# SensorBoard.net
KiCad netlist of a schematic drawn in Altium Designer
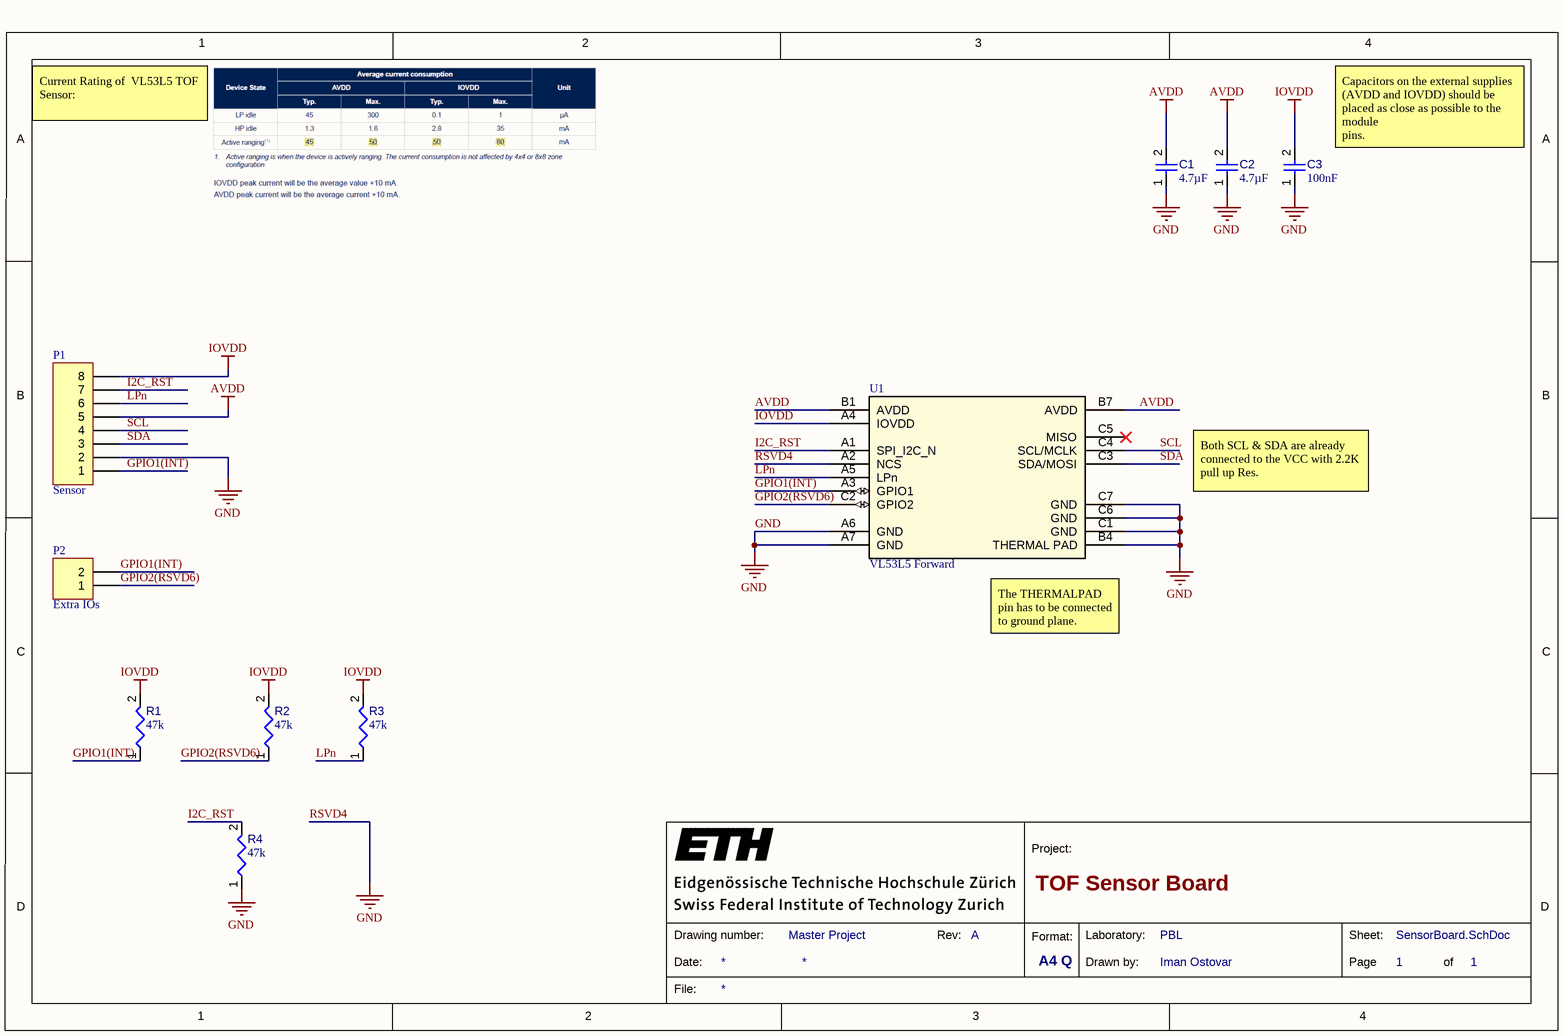
[diagram p0: SensorBoard.SchDoc]

(export (version "E")
  (design (tool "Eeschema 10.0.6"))
  (components
    (comp (ref "C1")
      (value "4.7µF")
      (footprint "CAPC1005X55X25ML5T10")
      (description "Chip Capacitor, 1 uF, +/- 10%, 6.3 V, 1005 (0402 Metric)")
      (fields (field (name "TOLERANCE") "10%") (field (name "Comment") "Capacitor 1 uF +/- 10% 6.3 V 1005"))
      (libsource (lib "ETH Zurich") (part "CAP-NP-2"))
    )
    (comp (ref "C2")
      (value "4.7µF")
      (footprint "CAPC1005X55X25ML5T10")
      (description "Chip Capacitor, 1 uF, +/- 10%, 6.3 V, 1005 (0402 Metric)")
      (fields (field (name "TOLERANCE") "10%") (field (name "Comment") "Capacitor 1 uF +/- 10% 6.3 V 1005"))
      (libsource (lib "ETH Zurich") (part "CAP-NP-2"))
    )
    (comp (ref "C3")
      (value "100nF")
      (footprint "CAPC0402(1005)60_L")
      (description "Chip Capacitor, 100nF +/-20%, 25V, 0402, Thickness 0.6 mm")
      (fields (field (name "TOLERANCE") "10%") (field (name "Comment") "Capacitor 100nF +/-20% 25V 0402"))
      (libsource (lib "ETH Zurich") (part "CAP-NP-2"))
    )
    (comp (ref "P1")
      (value "Sensor")
      (footprint "MHDR1X8")
      (description "Header, 8-Pin")
      (fields (field (name "PUBLISHER") "Altium Limited"))
      (libsource (lib "Miscellaneous Connectors") (part "MHDR1X8"))
    )
    (comp (ref "P2")
      (value "Extra IOs")
      (footprint "MHDR1X2")
      (description "Header, 2-Pin")
      (fields (field (name "PUBLISHER") "Altium Limited"))
      (libsource (lib "Miscellaneous Connectors") (part "MHDR1X2"))
    )
    (comp (ref "R1")
      (value "47k")
      (footprint "RESC0402(1005)_L")
      (description "Chip Resistor, 47,5 kOhms, +/-1 %, 63 mW, -55 to 155 degC, 0402")
      (fields (field (name "POWER") "63mW") (field (name "TOLERANCE") "1%"))
      (libsource (lib "ETH Zurich") (part "RES-2"))
    )
    (comp (ref "R2")
      (value "47k")
      (footprint "RESC0402(1005)_L")
      (description "Chip Resistor, 47,5 kOhms, +/-1 %, 63 mW, -55 to 155 degC, 0402")
      (fields (field (name "POWER") "63mW") (field (name "TOLERANCE") "1%"))
      (libsource (lib "ETH Zurich") (part "RES-2"))
    )
    (comp (ref "R3")
      (value "47k")
      (footprint "RESC0402(1005)_L")
      (description "Chip Resistor, 47,5 kOhms, +/-1 %, 63 mW, -55 to 155 degC, 0402")
      (fields (field (name "POWER") "63mW") (field (name "TOLERANCE") "1%"))
      (libsource (lib "ETH Zurich") (part "RES-2"))
    )
    (comp (ref "R4")
      (value "47k")
      (footprint "RESC0402(1005)_L")
      (description "Chip Resistor, 47,5 kOhms, +/-1 %, 63 mW, -55 to 155 degC, 0402")
      (fields (field (name "POWER") "63mW") (field (name "TOLERANCE") "1%"))
      (libsource (lib "ETH Zurich") (part "RES-2"))
    )
    (comp (ref "U1")
      (value "VL53L5 Forward")
      (footprint "ARRAY_53L5_STM")
      (description "No Description Available")
      (fields
        (field (name "MANUFACTURER_PART_NUMBER") "VL53L5")
        (field (name "COPYRIGHT") "Copyright (C) 2018 Accelerated Designs. All rights reserved")
      )
      (libsource (lib "VL53L5") (part "VL53L5"))
    )
  )
  (nets
    (net (code "1") (name "/GPIO1(INT)") (class "Default")
      (node (ref "P1") (pin "1") (pinfunction "1_1") (pintype "passive"))
      (node (ref "P2") (pin "2") (pinfunction "2_2") (pintype "passive"))
      (node (ref "R1") (pin "1") (pinfunction "1_1") (pintype "passive"))
      (node (ref "U1") (pin "A3") (pinfunction "GPIO1_A3") (pintype "bidirectional"))
    )
    (net (code "2") (name "/GPIO2(RSVD6)") (class "Default")
      (node (ref "P2") (pin "1") (pinfunction "1_1") (pintype "passive"))
      (node (ref "R2") (pin "1") (pinfunction "1_1") (pintype "passive"))
      (node (ref "U1") (pin "C2") (pinfunction "GPIO2_C2") (pintype "bidirectional"))
    )
    (net (code "3") (name "/I2C_RST") (class "Default")
      (node (ref "P1") (pin "7") (pinfunction "7_7") (pintype "passive"))
      (node (ref "R4") (pin "2") (pinfunction "2_2") (pintype "passive"))
      (node (ref "U1") (pin "A1") (pinfunction "SPI_I2C_N_A1") (pintype "passive"))
    )
    (net (code "4") (name "/LPn") (class "Default")
      (node (ref "P1") (pin "6") (pinfunction "6_6") (pintype "passive"))
      (node (ref "R3") (pin "1") (pinfunction "1_1") (pintype "passive"))
      (node (ref "U1") (pin "A5") (pinfunction "LPn_A5") (pintype "passive"))
    )
    (net (code "5") (name "/SCL") (class "Default")
      (node (ref "P1") (pin "4") (pinfunction "4_4") (pintype "passive"))
      (node (ref "U1") (pin "C4") (pinfunction "SCL/MCLK_C4") (pintype "passive"))
    )
    (net (code "6") (name "/SDA") (class "Default")
      (node (ref "P1") (pin "3") (pinfunction "3_3") (pintype "passive"))
      (node (ref "U1") (pin "C3") (pinfunction "SDA/MOSI_C3") (pintype "passive"))
    )
    (net (code "7") (name "AVDD") (class "Default")
      (node (ref "C1") (pin "2") (pinfunction "2_2") (pintype "passive"))
      (node (ref "C2") (pin "2") (pinfunction "2_2") (pintype "passive"))
      (node (ref "P1") (pin "5") (pinfunction "5_5") (pintype "passive"))
      (node (ref "U1") (pin "B1") (pinfunction "AVDD_B1") (pintype "power_in"))
      (node (ref "U1") (pin "B7") (pinfunction "AVDD_B7") (pintype "power_in"))
    )
    (net (code "8") (name "GND") (class "Default")
      (node (ref "C1") (pin "1") (pinfunction "1_1") (pintype "passive"))
      (node (ref "C2") (pin "1") (pinfunction "1_1") (pintype "passive"))
      (node (ref "C3") (pin "1") (pinfunction "1_1") (pintype "passive"))
      (node (ref "P1") (pin "2") (pinfunction "2_2") (pintype "passive"))
      (node (ref "R4") (pin "1") (pinfunction "1_1") (pintype "passive"))
      (node (ref "U1") (pin "A2") (pinfunction "NCS_A2") (pintype "passive"))
      (node (ref "U1") (pin "A6") (pinfunction "GND_A6") (pintype "passive"))
      (node (ref "U1") (pin "A7") (pinfunction "GND_A7") (pintype "passive"))
      (node (ref "U1") (pin "B4") (pinfunction "THERMAL_PAD_B4") (pintype "passive"))
      (node (ref "U1") (pin "C1") (pinfunction "GND_C1") (pintype "passive"))
      (node (ref "U1") (pin "C6") (pinfunction "GND_C6") (pintype "passive"))
      (node (ref "U1") (pin "C7") (pinfunction "GND_C7") (pintype "passive"))
    )
    (net (code "9") (name "IOVDD") (class "Default")
      (node (ref "C3") (pin "2") (pinfunction "2_2") (pintype "passive"))
      (node (ref "P1") (pin "8") (pinfunction "8_8") (pintype "passive"))
      (node (ref "R1") (pin "2") (pinfunction "2_2") (pintype "passive"))
      (node (ref "R2") (pin "2") (pinfunction "2_2") (pintype "passive"))
      (node (ref "R3") (pin "2") (pinfunction "2_2") (pintype "passive"))
      (node (ref "U1") (pin "A4") (pinfunction "IOVDD_A4") (pintype "power_in"))
    )
    (net (code "10") (name "unconnected-(U1-MISO-PadC5)") (class "Default")
      (node (ref "U1") (pin "C5") (pinfunction "MISO_C5") (pintype "passive+no_connect"))
    )
  )
)
